# DSI_LCD.net
KiCad netlist of a schematic drawn in Altium Designer
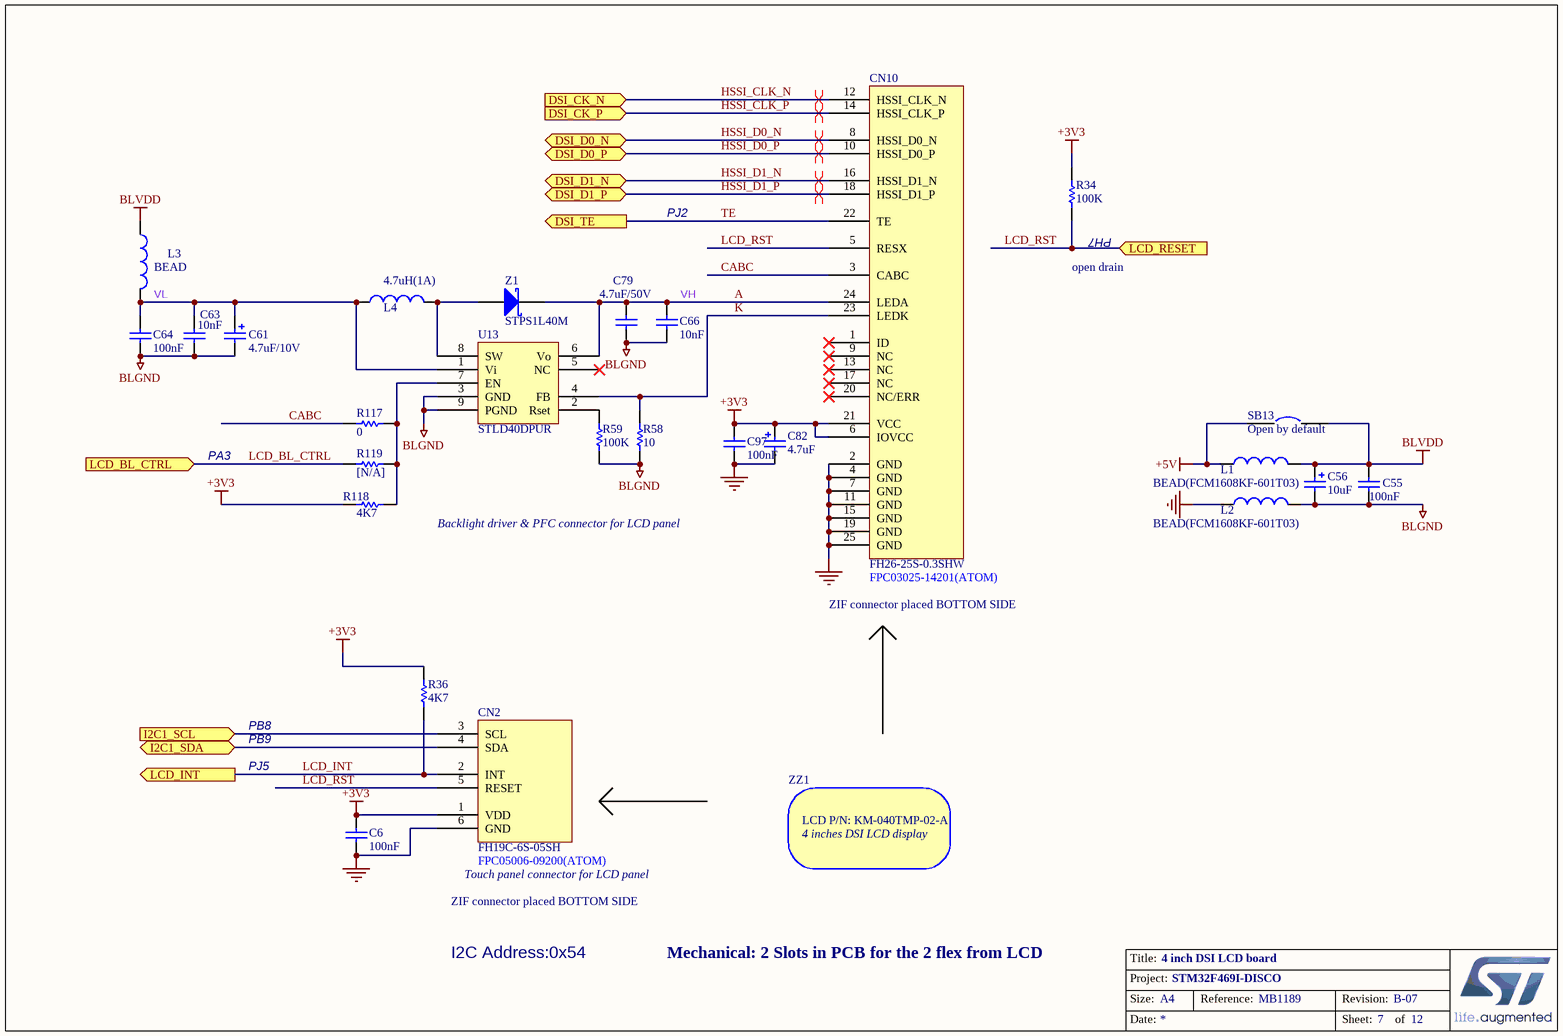
[diagram p0: DSI_LCD.SchDoc]

(export (version "E")
  (design (tool "Eeschema 10.0.6"))
  (components
    (comp (ref "C6")
      (value "100nF")
      (footprint "0402C")
      (description "Capacitor")
      (fields (field (name "PUBLISHER") "Altium Limited"))
      (libsource (lib "Miscellaneous Devices") (part "CAP"))
    )
    (comp (ref "C55")
      (value "100nF")
      (footprint "0402C")
      (description "Capacitor")
      (fields (field (name "PUBLISHER") "Altium Limited"))
      (libsource (lib "Miscellaneous Devices") (part "Cap"))
    )
    (comp (ref "C56")
      (value "10uF")
      (footprint "TAN-A")
      (description "Polarized Capacitor (Radial)")
      (fields (field (name "PUBLISHER") "Altium Limited"))
      (libsource (lib "Miscellaneous Devices") (part "Cap Pol1"))
    )
    (comp (ref "C61")
      (value "4.7uF/10V")
      (footprint "1206C")
      (description "Polarized Capacitor (Radial)")
      (fields (field (name "PUBLISHER") "Altium Limited"))
      (libsource (lib "Miscellaneous Devices") (part "Cap Pol1"))
    )
    (comp (ref "C63")
      (value "10nF")
      (footprint "0603C")
      (description "Capacitor")
      (fields (field (name "PUBLISHER") "Altium Limited"))
      (libsource (lib "Miscellaneous Devices") (part "CAP"))
    )
    (comp (ref "C64")
      (value "100nF")
      (footprint "0402C")
      (description "Capacitor")
      (fields (field (name "PUBLISHER") "Altium Limited"))
      (libsource (lib "Miscellaneous Devices") (part "CAP"))
    )
    (comp (ref "C66")
      (value "10nF")
      (footprint "0603C")
      (description "Capacitor")
      (fields (field (name "PUBLISHER") "Altium Limited"))
      (libsource (lib "*") (part "CAP"))
    )
    (comp (ref "C79")
      (value "4.7uF/50V")
      (footprint "1206C")
      (description "Capacitor")
      (fields (field (name "PUBLISHER") "Altium Limited"))
      (libsource (lib "Miscellaneous Devices") (part "CAP"))
    )
    (comp (ref "C82")
      (value "4.7uF")
      (footprint "TAN-A")
      (description "Polarized Capacitor (Radial)")
      (fields (field (name "PUBLISHER") "Altium Limited"))
      (libsource (lib "Miscellaneous Devices") (part "Cap Pol1"))
    )
    (comp (ref "C97")
      (value "100nF")
      (footprint "0402C")
      (description "Capacitor")
      (fields (field (name "PUBLISHER") "Altium Limited"))
      (libsource (lib "Miscellaneous Devices") (part "CAP"))
    )
    (comp (ref "CN2")
      (value "FH19C-6S-05SH")
      (footprint "FH19C-6S-0R5SH_FPC_CPT")
      (description "ZIF connector placed bottom side")
      (libsource (lib "MB1166") (part "FH19C-6S-05SH"))
    )
    (comp (ref "CN10")
      (value "FH26-25S-0.3SHW")
      (footprint "FPC25_FPC03025-1420")
      (description "ZIF connector placed bottom side")
      (libsource (lib "MB1166") (part "FH26-25S-0.3SHW"))
    )
    (comp (ref "L1")
      (value "BEAD(FCM1608KF-601T03)")
      (footprint "0603L")
      (description "Inductor")
      (fields (field (name "PUBLISHER") "Altium Limited"))
      (libsource (lib "Miscellaneous Devices") (part "Inductor"))
    )
    (comp (ref "L2")
      (value "BEAD(FCM1608KF-601T03)")
      (footprint "0603L")
      (description "Inductor")
      (fields (field (name "PUBLISHER") "Altium Limited"))
      (libsource (lib "Miscellaneous Devices") (part "Inductor"))
    )
    (comp (ref "L3")
      (value "BEAD")
      (footprint "0603L")
      (description "Inductor")
      (fields (field (name "PUBLISHER") "Altium Limited"))
      (libsource (lib "Miscellaneous Devices") (part "Inductor"))
    )
    (comp (ref "L4")
      (value "4.7uH(1A)")
      (footprint "1210L")
      (description "Inductor")
      (fields (field (name "PUBLISHER") "Altium Limited"))
      (libsource (lib "Miscellaneous Devices") (part "Inductor"))
    )
    (comp (ref "R34")
      (value "100K")
      (footprint "0402R")
      (description "Resistor")
      (fields (field (name "PUBLISHER") "Altium Limited"))
      (libsource (lib "Miscellaneous Devices") (part "Res1"))
    )
    (comp (ref "R36")
      (value "4K7")
      (footprint "0603R")
      (description "Resistor")
      (fields (field (name "PUBLISHER") "Altium Limited"))
      (libsource (lib "*") (part "Res1"))
    )
    (comp (ref "R58")
      (value "10")
      (footprint "0603R")
      (description "Resistor")
      (fields (field (name "PUBLISHER") "Altium Limited"))
      (libsource (lib "Miscellaneous Devices") (part "Res1"))
    )
    (comp (ref "R59")
      (value "100K")
      (footprint "0603R")
      (description "Resistor")
      (fields (field (name "PUBLISHER") "Altium Limited"))
      (libsource (lib "Miscellaneous Devices") (part "Res1"))
    )
    (comp (ref "R117")
      (value "0")
      (footprint "0603R")
      (description "Resistor")
      (fields (field (name "PUBLISHER") "Altium Limited"))
      (libsource (lib "Miscellaneous Devices") (part "Res1"))
    )
    (comp (ref "R118")
      (value "4K7")
      (footprint "0603R")
      (description "Resistor")
      (fields (field (name "PUBLISHER") "Altium Limited"))
      (libsource (lib "Miscellaneous Devices") (part "Res1"))
    )
    (comp (ref "R119")
      (value "[N/A]")
      (footprint "0603R")
      (description "Resistor")
      (fields (field (name "PUBLISHER") "Altium Limited"))
      (libsource (lib "Miscellaneous Devices") (part "Res1"))
    )
    (comp (ref "SB13")
      (value "Open by default")
      (footprint "SB_0603")
      (description "Circuit Breaker")
      (fields (field (name "PUBLISHER") "Altium Limited"))
      (libsource (lib "Miscellaneous Devices") (part "Circuit Breaker"))
    )
    (comp (ref "U13")
      (value "STLD40DPUR")
      (footprint "SON8_0R65_3X3")
      (libsource (lib "3.2LCD_daughterboard") (part "STLD40DPMR"))
    )
    (comp (ref "Z1")
      (value "STPS1L40M")
      (footprint "DO-216AA")
      (description "Schottky Diode")
      (fields (field (name "PUBLISHER") "Altium Limited"))
      (libsource (lib "Miscellaneous Devices") (part "D Schottky"))
    )
    (comp (ref "ZZ1")
      (value "LCD P/N: KM-040TMP-02-A")
      (description "4 inches DSI LCD with touch screen")
      (libsource (lib "Almos") (part "BoM_Item"))
    )
  )
  (nets
    (net (code "1") (name "+3V3") (class "Default")
      (node (ref "C6") (pin "2") (pinfunction "2_2") (pintype "passive"))
      (node (ref "C82") (pin "1") (pinfunction "1_1") (pintype "passive"))
      (node (ref "C97") (pin "2") (pinfunction "2_2") (pintype "passive"))
      (node (ref "CN10") (pin "21") (pinfunction "VCC_21") (pintype "passive"))
      (node (ref "CN10") (pin "6") (pinfunction "IOVCC_6") (pintype "passive"))
      (node (ref "CN2") (pin "1") (pinfunction "VDD_1") (pintype "passive"))
      (node (ref "R118") (pin "2") (pinfunction "2_2") (pintype "passive"))
      (node (ref "R34") (pin "1") (pinfunction "1_1") (pintype "passive"))
      (node (ref "R36") (pin "1") (pinfunction "1_1") (pintype "passive"))
    )
    (net (code "2") (name "+5V") (class "Default")
      (node (ref "L1") (pin "1") (pinfunction "1_1") (pintype "passive"))
      (node (ref "SB13") (pin "1") (pinfunction "1_1") (pintype "passive"))
    )
    (net (code "3") (name "/A") (class "Default")
      (node (ref "C66") (pin "2") (pinfunction "2_2") (pintype "passive"))
      (node (ref "C79") (pin "1") (pinfunction "1_1") (pintype "passive"))
      (node (ref "CN10") (pin "24") (pinfunction "LEDA_24") (pintype "passive"))
      (node (ref "U13") (pin "6") (pinfunction "Vo_6") (pintype "passive"))
      (node (ref "Z1") (pin "2") (pinfunction "K_2") (pintype "passive"))
    )
    (net (code "4") (name "/CABC") (class "Default")
      (node (ref "CN10") (pin "3") (pinfunction "CABC_3") (pintype "passive"))
      (node (ref "R117") (pin "2") (pinfunction "2_2") (pintype "passive"))
    )
    (net (code "5") (name "/HSSI_CLK_N") (class "Default")
      (node (ref "CN10") (pin "12") (pinfunction "HSSI_CLK_N_12") (pintype "passive"))
    )
    (net (code "6") (name "/HSSI_CLK_P") (class "Default")
      (node (ref "CN10") (pin "14") (pinfunction "HSSI_CLK_P_14") (pintype "passive"))
    )
    (net (code "7") (name "/HSSI_D0_N") (class "Default")
      (node (ref "CN10") (pin "8") (pinfunction "HSSI_D0_N_8") (pintype "passive"))
    )
    (net (code "8") (name "/HSSI_D0_P") (class "Default")
      (node (ref "CN10") (pin "10") (pinfunction "HSSI_D0_P_10") (pintype "passive"))
    )
    (net (code "9") (name "/HSSI_D1_N") (class "Default")
      (node (ref "CN10") (pin "16") (pinfunction "HSSI_D1_N_16") (pintype "passive"))
    )
    (net (code "10") (name "/HSSI_D1_P") (class "Default")
      (node (ref "CN10") (pin "18") (pinfunction "HSSI_D1_P_18") (pintype "passive"))
    )
    (net (code "11") (name "/I2C1_SCL") (class "Default")
      (node (ref "CN2") (pin "3") (pinfunction "SCL_3") (pintype "passive"))
    )
    (net (code "12") (name "/I2C1_SDA") (class "Default")
      (node (ref "CN2") (pin "4") (pinfunction "SDA_4") (pintype "passive"))
    )
    (net (code "13") (name "/K") (class "Default")
      (node (ref "CN10") (pin "23") (pinfunction "LEDK_23") (pintype "passive"))
      (node (ref "R58") (pin "2") (pinfunction "2_2") (pintype "passive"))
      (node (ref "U13") (pin "4") (pinfunction "FB_4") (pintype "passive"))
    )
    (net (code "14") (name "/LCD_BL_CTRL") (class "Default")
      (node (ref "R119") (pin "2") (pinfunction "2_2") (pintype "passive"))
    )
    (net (code "15") (name "/LCD_INT") (class "Default")
      (node (ref "CN2") (pin "2") (pinfunction "INT_2") (pintype "passive"))
      (node (ref "R36") (pin "2") (pinfunction "2_2") (pintype "passive"))
    )
    (net (code "16") (name "/LCD_RST") (class "Default")
      (node (ref "CN10") (pin "5") (pinfunction "RESX_5") (pintype "passive"))
      (node (ref "CN2") (pin "5") (pinfunction "RESET_5") (pintype "passive"))
      (node (ref "R34") (pin "2") (pinfunction "2_2") (pintype "passive"))
    )
    (net (code "17") (name "/TE") (class "Default")
      (node (ref "CN10") (pin "22") (pinfunction "TE_22") (pintype "passive"))
    )
    (net (code "18") (name "/VL") (class "Default")
      (node (ref "C61") (pin "1") (pinfunction "1_1") (pintype "passive"))
      (node (ref "C63") (pin "2") (pinfunction "2_2") (pintype "passive"))
      (node (ref "C64") (pin "2") (pinfunction "2_2") (pintype "passive"))
      (node (ref "L3") (pin "2") (pinfunction "2_2") (pintype "passive"))
      (node (ref "L4") (pin "1") (pinfunction "1_1") (pintype "passive"))
      (node (ref "U13") (pin "1") (pinfunction "Vi_1") (pintype "passive"))
    )
    (net (code "19") (name "BLGND") (class "Default")
      (node (ref "C55") (pin "2") (pinfunction "2_2") (pintype "passive"))
      (node (ref "C56") (pin "2") (pinfunction "2_2") (pintype "passive"))
      (node (ref "C61") (pin "2") (pinfunction "2_2") (pintype "passive"))
      (node (ref "C63") (pin "1") (pinfunction "1_1") (pintype "passive"))
      (node (ref "C64") (pin "1") (pinfunction "1_1") (pintype "passive"))
      (node (ref "C66") (pin "1") (pinfunction "1_1") (pintype "passive"))
      (node (ref "C79") (pin "2") (pinfunction "2_2") (pintype "passive"))
      (node (ref "L2") (pin "2") (pinfunction "2_2") (pintype "passive"))
      (node (ref "R58") (pin "1") (pinfunction "1_1") (pintype "passive"))
      (node (ref "R59") (pin "2") (pinfunction "2_2") (pintype "passive"))
      (node (ref "U13") (pin "3") (pinfunction "GND_3") (pintype "passive"))
      (node (ref "U13") (pin "9") (pinfunction "PGND_9") (pintype "passive"))
    )
    (net (code "20") (name "BLVDD") (class "Default")
      (node (ref "C55") (pin "1") (pinfunction "1_1") (pintype "passive"))
      (node (ref "C56") (pin "1") (pinfunction "1_1") (pintype "passive"))
      (node (ref "L1") (pin "2") (pinfunction "2_2") (pintype "passive"))
      (node (ref "L3") (pin "1") (pinfunction "1_1") (pintype "passive"))
      (node (ref "SB13") (pin "2") (pinfunction "2_2") (pintype "passive"))
    )
    (net (code "21") (name "GND") (class "Default")
      (node (ref "C6") (pin "1") (pinfunction "1_1") (pintype "passive"))
      (node (ref "C82") (pin "2") (pinfunction "2_2") (pintype "passive"))
      (node (ref "C97") (pin "1") (pinfunction "1_1") (pintype "passive"))
      (node (ref "CN10") (pin "11") (pinfunction "GND_11") (pintype "passive"))
      (node (ref "CN10") (pin "15") (pinfunction "GND_15") (pintype "passive"))
      (node (ref "CN10") (pin "19") (pinfunction "GND_19") (pintype "passive"))
      (node (ref "CN10") (pin "2") (pinfunction "GND_2") (pintype "passive"))
      (node (ref "CN10") (pin "25") (pinfunction "GND_25") (pintype "passive"))
      (node (ref "CN10") (pin "4") (pinfunction "GND_4") (pintype "passive"))
      (node (ref "CN10") (pin "7") (pinfunction "GND_7") (pintype "passive"))
      (node (ref "CN2") (pin "6") (pinfunction "GND_6") (pintype "passive"))
      (node (ref "L2") (pin "1") (pinfunction "1_1") (pintype "passive"))
    )
    (net (code "22") (name "Net-(U13-EN)") (class "Default")
      (node (ref "R117") (pin "1") (pinfunction "1_1") (pintype "passive"))
      (node (ref "R118") (pin "1") (pinfunction "1_1") (pintype "passive"))
      (node (ref "R119") (pin "1") (pinfunction "1_1") (pintype "passive"))
      (node (ref "U13") (pin "7") (pinfunction "EN_7") (pintype "passive"))
    )
    (net (code "23") (name "Net-(U13-Rset)") (class "Default")
      (node (ref "R59") (pin "1") (pinfunction "1_1") (pintype "passive"))
      (node (ref "U13") (pin "2") (pinfunction "Rset_2") (pintype "passive"))
    )
    (net (code "24") (name "Net-(U13-SW)") (class "Default")
      (node (ref "L4") (pin "2") (pinfunction "2_2") (pintype "passive"))
      (node (ref "U13") (pin "8") (pinfunction "SW_8") (pintype "passive"))
      (node (ref "Z1") (pin "1") (pinfunction "A_1") (pintype "passive"))
    )
    (net (code "25") (name "unconnected-(CN10-ID-Pad1)") (class "Default")
      (node (ref "CN10") (pin "1") (pinfunction "ID_1") (pintype "passive+no_connect"))
    )
    (net (code "26") (name "unconnected-(CN10-NC-Pad9)") (class "Default")
      (node (ref "CN10") (pin "9") (pinfunction "NC_9") (pintype "passive+no_connect"))
    )
    (net (code "27") (name "unconnected-(CN10-NC-Pad13)") (class "Default")
      (node (ref "CN10") (pin "13") (pinfunction "NC_13") (pintype "passive+no_connect"))
    )
    (net (code "28") (name "unconnected-(CN10-NC-Pad17)") (class "Default")
      (node (ref "CN10") (pin "17") (pinfunction "NC_17") (pintype "passive+no_connect"))
    )
    (net (code "29") (name "unconnected-(CN10-NC{slash}ERR-Pad20)") (class "Default")
      (node (ref "CN10") (pin "20") (pinfunction "NC/ERR_20") (pintype "passive+no_connect"))
    )
    (net (code "30") (name "unconnected-(U13-NC-Pad5)") (class "Default")
      (node (ref "U13") (pin "5") (pinfunction "NC_5") (pintype "passive+no_connect"))
    )
  )
)
